# spielfeld_anzeige.net
KiCad netlist of a schematic drawn in EAGLE
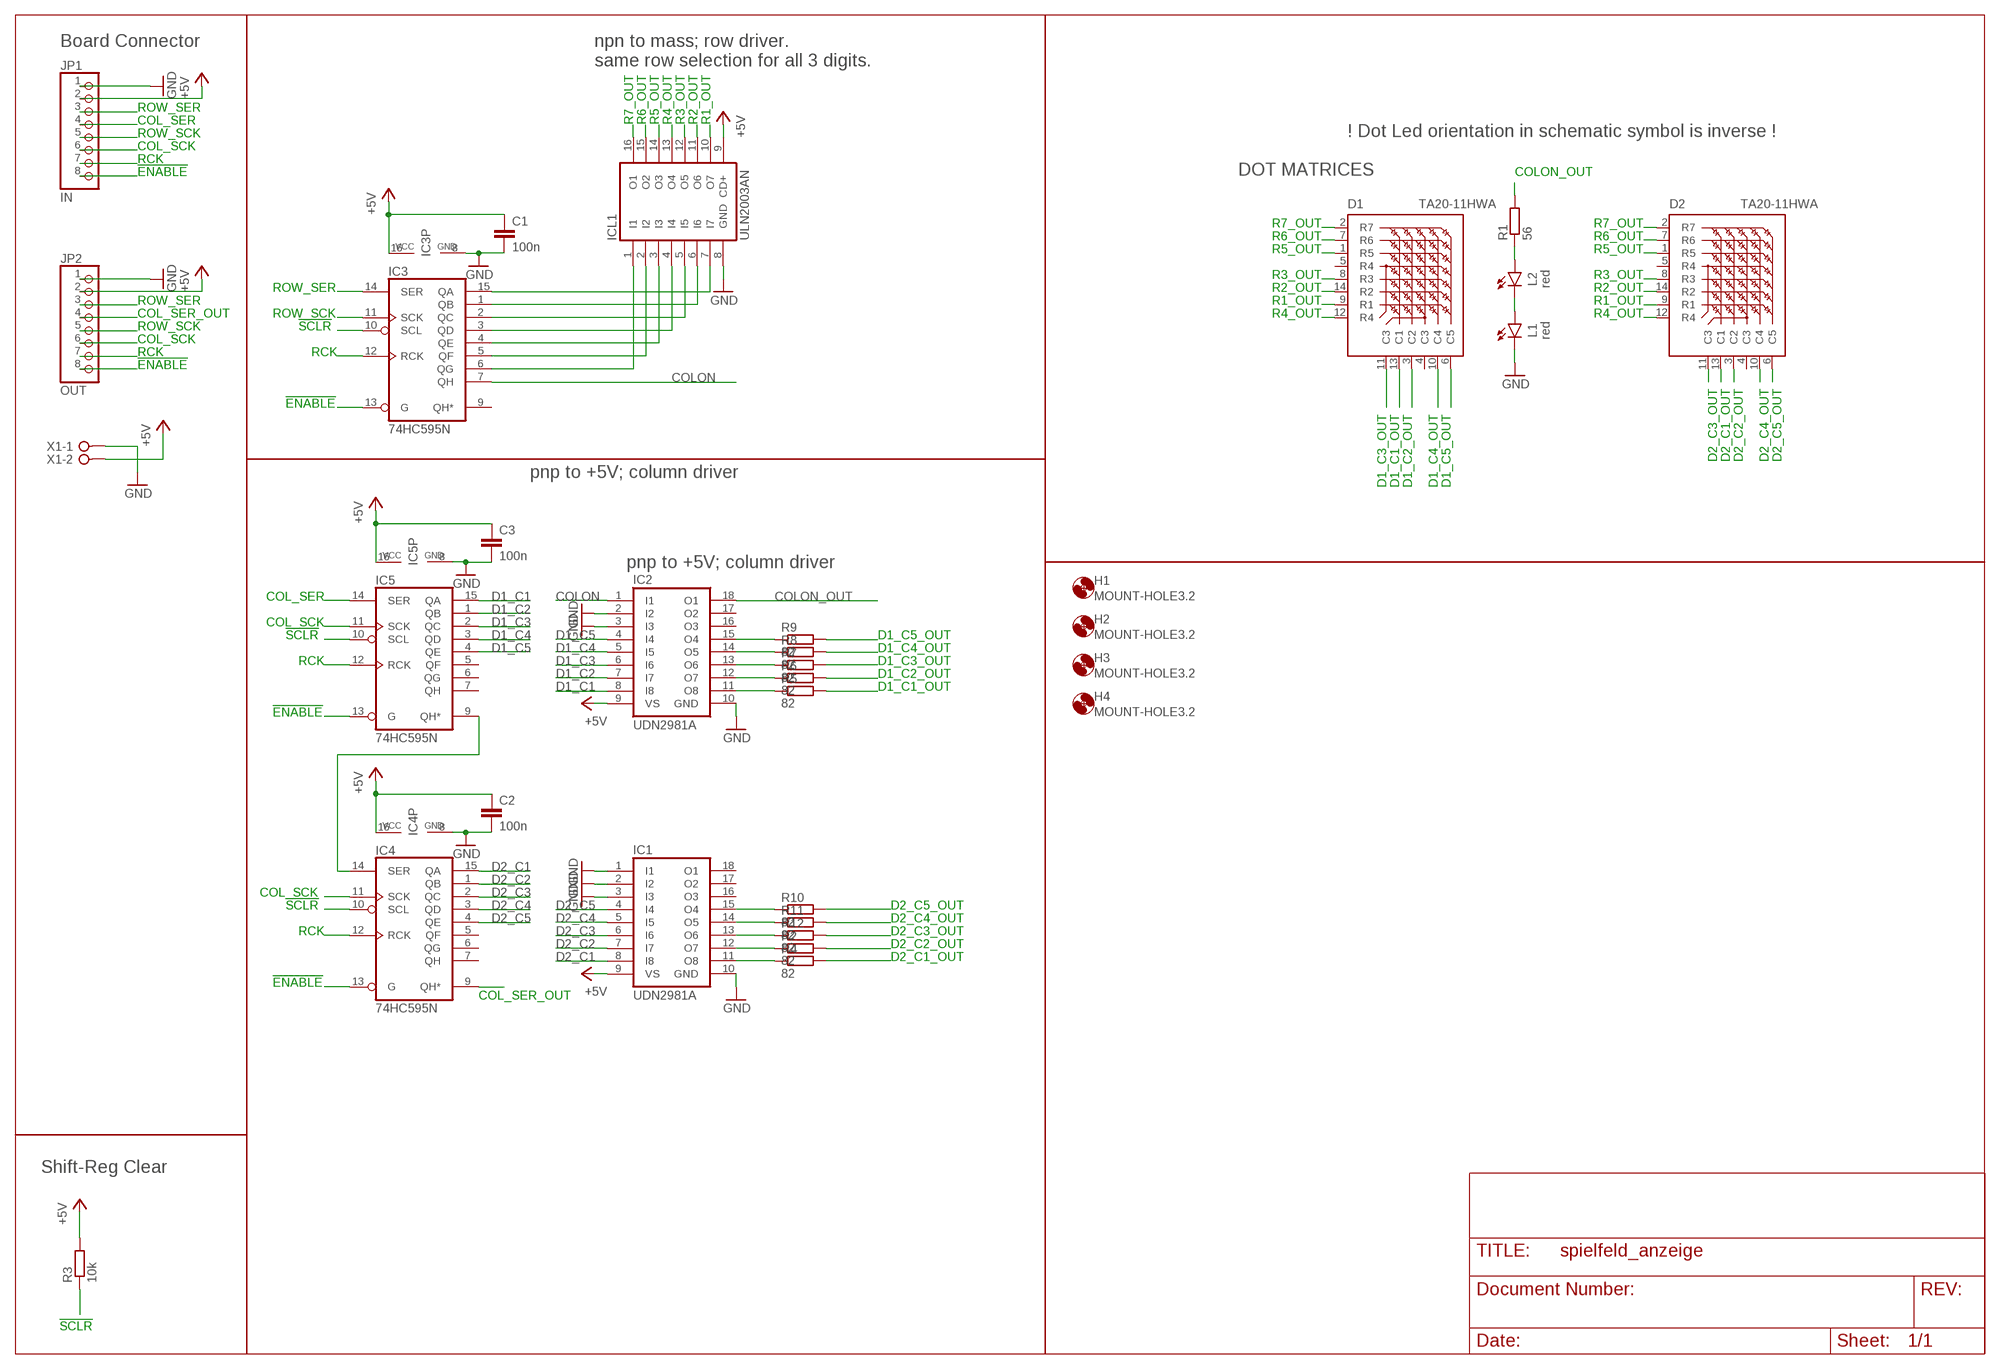
[diagram p0: schematic, sheet 1]

(export (version "E")
  (design (tool "Eeschema 10.0.6"))
  (components
    (comp (ref "C1")
      (value "100n")
      (footprint "eagle-import:C0805")
      (libsource (lib "eagle-import") (part "C-EUC0805"))
    )
    (comp (ref "C2")
      (value "100n")
      (footprint "eagle-import:C0805")
      (libsource (lib "eagle-import") (part "C-EUC0805"))
    )
    (comp (ref "C3")
      (value "100n")
      (footprint "eagle-import:C0805")
      (libsource (lib "eagle-import") (part "C-EUC0805"))
    )
    (comp (ref "D1")
      (value "TA20-11HWA")
      (footprint "eagle-import:TA20-11HWA")
      (libsource (lib "eagle-import") (part "TA20-11HWA"))
    )
    (comp (ref "D2")
      (value "TA20-11HWA")
      (footprint "eagle-import:TA20-11HWA")
      (libsource (lib "eagle-import") (part "TA20-11HWA"))
    )
    (comp (ref "H1")
      (value "MOUNT-HOLE3.2")
      (footprint "eagle-import:3,2")
      (libsource (lib "eagle-import") (part "MOUNT-HOLE3.2"))
    )
    (comp (ref "H2")
      (value "MOUNT-HOLE3.2")
      (footprint "eagle-import:3,2")
      (libsource (lib "eagle-import") (part "MOUNT-HOLE3.2"))
    )
    (comp (ref "H3")
      (value "MOUNT-HOLE3.2")
      (footprint "eagle-import:3,2")
      (libsource (lib "eagle-import") (part "MOUNT-HOLE3.2"))
    )
    (comp (ref "H4")
      (value "MOUNT-HOLE3.2")
      (footprint "eagle-import:3,2")
      (libsource (lib "eagle-import") (part "MOUNT-HOLE3.2"))
    )
    (comp (ref "IC1")
      (value "UDN2981A")
      (footprint "eagle-import:DIL18")
      (libsource (lib "eagle-import") (part "UDN298A1"))
    )
    (comp (ref "IC2")
      (value "UDN2981A")
      (footprint "eagle-import:DIL18")
      (libsource (lib "eagle-import") (part "UDN298A1"))
    )
    (comp (ref "IC3")
      (value "74HC595N")
      (footprint "eagle-import:DIL16")
      (libsource (lib "eagle-import") (part "74595NHC"))
    )
    (comp (ref "IC4")
      (value "74HC595N")
      (footprint "eagle-import:DIL16")
      (libsource (lib "eagle-import") (part "74595NHC"))
    )
    (comp (ref "IC5")
      (value "74HC595N")
      (footprint "eagle-import:DIL16")
      (libsource (lib "eagle-import") (part "74595NHC"))
    )
    (comp (ref "ICL1")
      (value "ULN2003AN")
      (footprint "eagle-import:DIL16")
      (libsource (lib "eagle-import") (part "ULN2003AN"))
    )
    (comp (ref "JP1")
      (value "IN")
      (footprint "eagle-import:1X08")
      (libsource (lib "eagle-import") (part "PINHD-1X8"))
    )
    (comp (ref "JP2")
      (value "OUT")
      (footprint "eagle-import:1X08")
      (libsource (lib "eagle-import") (part "PINHD-1X8"))
    )
    (comp (ref "L1")
      (value "red")
      (footprint "eagle-import:LED_5MM")
      (libsource (lib "eagle-import") (part "LED-5MM"))
    )
    (comp (ref "L2")
      (value "red")
      (footprint "eagle-import:LED_5MM")
      (libsource (lib "eagle-import") (part "LED-5MM"))
    )
    (comp (ref "R1")
      (value "56")
      (footprint "eagle-import:R3216")
      (libsource (lib "eagle-import") (part "R-EU_R3216"))
    )
    (comp (ref "R2")
      (value "82")
      (footprint "eagle-import:R0805")
      (libsource (lib "eagle-import") (part "R-EU_R0805"))
    )
    (comp (ref "R3")
      (value "10k")
      (footprint "eagle-import:M3216")
      (libsource (lib "eagle-import") (part "resistor_R-EU_M3216"))
    )
    (comp (ref "R4")
      (value "82")
      (footprint "eagle-import:R0805")
      (libsource (lib "eagle-import") (part "R-EU_R0805"))
    )
    (comp (ref "R5")
      (value "82")
      (footprint "eagle-import:R0805")
      (libsource (lib "eagle-import") (part "R-EU_R0805"))
    )
    (comp (ref "R6")
      (value "82")
      (footprint "eagle-import:R0805")
      (libsource (lib "eagle-import") (part "R-EU_R0805"))
    )
    (comp (ref "R7")
      (value "82")
      (footprint "eagle-import:R0805")
      (libsource (lib "eagle-import") (part "R-EU_R0805"))
    )
    (comp (ref "R8")
      (value "82")
      (footprint "eagle-import:R0805")
      (libsource (lib "eagle-import") (part "R-EU_R0805"))
    )
    (comp (ref "R9")
      (value "82")
      (footprint "eagle-import:R0805")
      (libsource (lib "eagle-import") (part "R-EU_R0805"))
    )
    (comp (ref "R10")
      (value "82")
      (footprint "eagle-import:R0805")
      (libsource (lib "eagle-import") (part "R-EU_R0805"))
    )
    (comp (ref "R11")
      (value "82")
      (footprint "eagle-import:R0805")
      (libsource (lib "eagle-import") (part "R-EU_R0805"))
    )
    (comp (ref "R12")
      (value "82")
      (footprint "eagle-import:R0805")
      (libsource (lib "eagle-import") (part "R-EU_R0805"))
    )
    (comp (ref "X1")
      (value "W237-02P")
      (footprint "eagle-import:W237-132")
      (libsource (lib "eagle-import") (part "W237-02P"))
    )
  )
  (nets
    (net (code "1") (name "+5V") (class "Default")
      (node (ref "C1") (pin "1") (pinfunction "1_1") (pintype "passive"))
      (node (ref "C2") (pin "1") (pinfunction "1_1") (pintype "passive"))
      (node (ref "C3") (pin "1") (pinfunction "1_1") (pintype "passive"))
      (node (ref "IC1") (pin "9") (pinfunction "VS_9") (pintype "passive"))
      (node (ref "IC2") (pin "9") (pinfunction "VS_9") (pintype "passive"))
      (node (ref "IC3") (pin "16") (pinfunction "VCC_16") (pintype "power_in"))
      (node (ref "IC4") (pin "16") (pinfunction "VCC_16") (pintype "power_in"))
      (node (ref "IC5") (pin "16") (pinfunction "VCC_16") (pintype "power_in"))
      (node (ref "ICL1") (pin "9") (pinfunction "CD+_9") (pintype "passive"))
      (node (ref "JP1") (pin "2") (pinfunction "2_2") (pintype "passive"))
      (node (ref "JP2") (pin "2") (pinfunction "2_2") (pintype "passive"))
      (node (ref "R3") (pin "2") (pinfunction "2_2") (pintype "passive"))
      (node (ref "X1") (pin "2") (pinfunction "KL_2") (pintype "passive"))
    )
    (net (code "2") (name "/COLON") (class "Default")
      (node (ref "IC2") (pin "1") (pinfunction "I1_1") (pintype "input"))
      (node (ref "IC3") (pin "7") (pinfunction "QH_7") (pintype "tri_state"))
    )
    (net (code "3") (name "/COLON_OUT") (class "Default")
      (node (ref "IC2") (pin "18") (pinfunction "O1_18") (pintype "open_collector"))
      (node (ref "R1") (pin "2") (pinfunction "2_2") (pintype "passive"))
    )
    (net (code "4") (name "/COL_SCK") (class "Default")
      (node (ref "IC4") (pin "11") (pinfunction "SCK_11") (pintype "input"))
      (node (ref "IC5") (pin "11") (pinfunction "SCK_11") (pintype "input"))
      (node (ref "JP1") (pin "6") (pinfunction "6_6") (pintype "passive"))
      (node (ref "JP2") (pin "6") (pinfunction "6_6") (pintype "passive"))
    )
    (net (code "5") (name "/COL_SER") (class "Default")
      (node (ref "IC5") (pin "14") (pinfunction "SER_14") (pintype "input"))
      (node (ref "JP1") (pin "4") (pinfunction "4_4") (pintype "passive"))
    )
    (net (code "6") (name "/COL_SER_OUT") (class "Default")
      (node (ref "IC4") (pin "9") (pinfunction "QH*_9") (pintype "tri_state"))
      (node (ref "JP2") (pin "4") (pinfunction "4_4") (pintype "passive"))
    )
    (net (code "7") (name "/D1_C1") (class "Default")
      (node (ref "IC2") (pin "8") (pinfunction "I8_8") (pintype "input"))
      (node (ref "IC5") (pin "15") (pinfunction "QA_15") (pintype "tri_state"))
    )
    (net (code "8") (name "/D1_C1_OUT") (class "Default")
      (node (ref "D1") (pin "13") (pinfunction "C1_13") (pintype "passive"))
      (node (ref "R5") (pin "2") (pinfunction "2_2") (pintype "passive"))
    )
    (net (code "9") (name "/D1_C2") (class "Default")
      (node (ref "IC2") (pin "7") (pinfunction "I7_7") (pintype "input"))
      (node (ref "IC5") (pin "1") (pinfunction "QB_1") (pintype "tri_state"))
    )
    (net (code "10") (name "/D1_C2_OUT") (class "Default")
      (node (ref "D1") (pin "3") (pinfunction "C2_3") (pintype "passive"))
      (node (ref "R6") (pin "2") (pinfunction "2_2") (pintype "passive"))
    )
    (net (code "11") (name "/D1_C3") (class "Default")
      (node (ref "IC2") (pin "6") (pinfunction "I6_6") (pintype "input"))
      (node (ref "IC5") (pin "2") (pinfunction "QC_2") (pintype "tri_state"))
    )
    (net (code "12") (name "/D1_C3_OUT") (class "Default")
      (node (ref "D1") (pin "11") (pinfunction "C3_11") (pintype "passive"))
      (node (ref "R7") (pin "2") (pinfunction "2_2") (pintype "passive"))
    )
    (net (code "13") (name "/D1_C4") (class "Default")
      (node (ref "IC2") (pin "5") (pinfunction "I5_5") (pintype "input"))
      (node (ref "IC5") (pin "3") (pinfunction "QD_3") (pintype "tri_state"))
    )
    (net (code "14") (name "/D1_C4_OUT") (class "Default")
      (node (ref "D1") (pin "10") (pinfunction "C4_10") (pintype "passive"))
      (node (ref "R8") (pin "2") (pinfunction "2_2") (pintype "passive"))
    )
    (net (code "15") (name "/D1_C5") (class "Default")
      (node (ref "IC2") (pin "4") (pinfunction "I4_4") (pintype "input"))
      (node (ref "IC5") (pin "4") (pinfunction "QE_4") (pintype "tri_state"))
    )
    (net (code "16") (name "/D1_C5_OUT") (class "Default")
      (node (ref "D1") (pin "6") (pinfunction "C5_6") (pintype "passive"))
      (node (ref "R9") (pin "2") (pinfunction "2_2") (pintype "passive"))
    )
    (net (code "17") (name "/D2_C1") (class "Default")
      (node (ref "IC1") (pin "8") (pinfunction "I8_8") (pintype "input"))
      (node (ref "IC4") (pin "15") (pinfunction "QA_15") (pintype "tri_state"))
    )
    (net (code "18") (name "/D2_C1_OUT") (class "Default")
      (node (ref "D2") (pin "13") (pinfunction "C1_13") (pintype "passive"))
      (node (ref "R4") (pin "2") (pinfunction "2_2") (pintype "passive"))
    )
    (net (code "19") (name "/D2_C2") (class "Default")
      (node (ref "IC1") (pin "7") (pinfunction "I7_7") (pintype "input"))
      (node (ref "IC4") (pin "1") (pinfunction "QB_1") (pintype "tri_state"))
    )
    (net (code "20") (name "/D2_C2_OUT") (class "Default")
      (node (ref "D2") (pin "3") (pinfunction "C2_3") (pintype "passive"))
      (node (ref "R2") (pin "2") (pinfunction "2_2") (pintype "passive"))
    )
    (net (code "21") (name "/D2_C3") (class "Default")
      (node (ref "IC1") (pin "6") (pinfunction "I6_6") (pintype "input"))
      (node (ref "IC4") (pin "2") (pinfunction "QC_2") (pintype "tri_state"))
    )
    (net (code "22") (name "/D2_C3_OUT") (class "Default")
      (node (ref "D2") (pin "11") (pinfunction "C3_11") (pintype "passive"))
      (node (ref "R12") (pin "2") (pinfunction "2_2") (pintype "passive"))
    )
    (net (code "23") (name "/D2_C4") (class "Default")
      (node (ref "IC1") (pin "5") (pinfunction "I5_5") (pintype "input"))
      (node (ref "IC4") (pin "3") (pinfunction "QD_3") (pintype "tri_state"))
    )
    (net (code "24") (name "/D2_C4_OUT") (class "Default")
      (node (ref "D2") (pin "10") (pinfunction "C4_10") (pintype "passive"))
      (node (ref "R11") (pin "2") (pinfunction "2_2") (pintype "passive"))
    )
    (net (code "25") (name "/D2_C5") (class "Default")
      (node (ref "IC1") (pin "4") (pinfunction "I4_4") (pintype "input"))
      (node (ref "IC4") (pin "4") (pinfunction "QE_4") (pintype "tri_state"))
    )
    (net (code "26") (name "/D2_C5_OUT") (class "Default")
      (node (ref "D2") (pin "6") (pinfunction "C5_6") (pintype "passive"))
      (node (ref "R10") (pin "2") (pinfunction "2_2") (pintype "passive"))
    )
    (net (code "27") (name "/R1_OUT") (class "Default")
      (node (ref "D1") (pin "9") (pinfunction "R1_9") (pintype "passive"))
      (node (ref "D2") (pin "9") (pinfunction "R1_9") (pintype "passive"))
      (node (ref "ICL1") (pin "10") (pinfunction "O7_10") (pintype "open_collector"))
    )
    (net (code "28") (name "/R2_OUT") (class "Default")
      (node (ref "D1") (pin "14") (pinfunction "R2_14") (pintype "passive"))
      (node (ref "D2") (pin "14") (pinfunction "R2_14") (pintype "passive"))
      (node (ref "ICL1") (pin "11") (pinfunction "O6_11") (pintype "open_collector"))
    )
    (net (code "29") (name "/R3_OUT") (class "Default")
      (node (ref "D1") (pin "8") (pinfunction "R3_8") (pintype "passive"))
      (node (ref "D2") (pin "8") (pinfunction "R3_8") (pintype "passive"))
      (node (ref "ICL1") (pin "12") (pinfunction "O5_12") (pintype "open_collector"))
    )
    (net (code "30") (name "/R4_OUT") (class "Default")
      (node (ref "D1") (pin "12") (pinfunction "R4_12") (pintype "passive"))
      (node (ref "D2") (pin "12") (pinfunction "R4_12") (pintype "passive"))
      (node (ref "ICL1") (pin "13") (pinfunction "O4_13") (pintype "open_collector"))
    )
    (net (code "31") (name "/R5_OUT") (class "Default")
      (node (ref "D1") (pin "1") (pinfunction "R5_1") (pintype "passive"))
      (node (ref "D2") (pin "1") (pinfunction "R5_1") (pintype "passive"))
      (node (ref "ICL1") (pin "14") (pinfunction "O3_14") (pintype "open_collector"))
    )
    (net (code "32") (name "/R6_OUT") (class "Default")
      (node (ref "D1") (pin "7") (pinfunction "R6_7") (pintype "passive"))
      (node (ref "D2") (pin "7") (pinfunction "R6_7") (pintype "passive"))
      (node (ref "ICL1") (pin "15") (pinfunction "O2_15") (pintype "open_collector"))
    )
    (net (code "33") (name "/R7_OUT") (class "Default")
      (node (ref "D1") (pin "2") (pinfunction "R7_2") (pintype "passive"))
      (node (ref "D2") (pin "2") (pinfunction "R7_2") (pintype "passive"))
      (node (ref "ICL1") (pin "16") (pinfunction "O1_16") (pintype "open_collector"))
    )
    (net (code "34") (name "/RCK") (class "Default")
      (node (ref "IC3") (pin "12") (pinfunction "RCK_12") (pintype "input"))
      (node (ref "IC4") (pin "12") (pinfunction "RCK_12") (pintype "input"))
      (node (ref "IC5") (pin "12") (pinfunction "RCK_12") (pintype "input"))
      (node (ref "JP1") (pin "7") (pinfunction "7_7") (pintype "passive"))
      (node (ref "JP2") (pin "7") (pinfunction "7_7") (pintype "passive"))
    )
    (net (code "35") (name "/ROW_SCK") (class "Default")
      (node (ref "IC3") (pin "11") (pinfunction "SCK_11") (pintype "input"))
      (node (ref "JP1") (pin "5") (pinfunction "5_5") (pintype "passive"))
      (node (ref "JP2") (pin "5") (pinfunction "5_5") (pintype "passive"))
    )
    (net (code "36") (name "/ROW_SER") (class "Default")
      (node (ref "IC3") (pin "14") (pinfunction "SER_14") (pintype "input"))
      (node (ref "JP1") (pin "3") (pinfunction "3_3") (pintype "passive"))
      (node (ref "JP2") (pin "3") (pinfunction "3_3") (pintype "passive"))
    )
    (net (code "37") (name "/~{ENABLE}") (class "Default")
      (node (ref "IC3") (pin "13") (pinfunction "G_13") (pintype "input"))
      (node (ref "IC4") (pin "13") (pinfunction "G_13") (pintype "input"))
      (node (ref "IC5") (pin "13") (pinfunction "G_13") (pintype "input"))
      (node (ref "JP1") (pin "8") (pinfunction "8_8") (pintype "passive"))
      (node (ref "JP2") (pin "8") (pinfunction "8_8") (pintype "passive"))
    )
    (net (code "38") (name "/~{SCLR}") (class "Default")
      (node (ref "IC3") (pin "10") (pinfunction "SCL_10") (pintype "input"))
      (node (ref "IC4") (pin "10") (pinfunction "SCL_10") (pintype "input"))
      (node (ref "IC5") (pin "10") (pinfunction "SCL_10") (pintype "input"))
      (node (ref "R3") (pin "1") (pinfunction "1_1") (pintype "passive"))
    )
    (net (code "39") (name "GND") (class "Default")
      (node (ref "C1") (pin "2") (pinfunction "2_2") (pintype "passive"))
      (node (ref "C2") (pin "2") (pinfunction "2_2") (pintype "passive"))
      (node (ref "C3") (pin "2") (pinfunction "2_2") (pintype "passive"))
      (node (ref "IC1") (pin "1") (pinfunction "I1_1") (pintype "input"))
      (node (ref "IC1") (pin "10") (pinfunction "GND_10") (pintype "power_in"))
      (node (ref "IC1") (pin "2") (pinfunction "I2_2") (pintype "input"))
      (node (ref "IC1") (pin "3") (pinfunction "I3_3") (pintype "input"))
      (node (ref "IC2") (pin "10") (pinfunction "GND_10") (pintype "power_in"))
      (node (ref "IC2") (pin "2") (pinfunction "I2_2") (pintype "input"))
      (node (ref "IC2") (pin "3") (pinfunction "I3_3") (pintype "input"))
      (node (ref "IC3") (pin "8") (pinfunction "GND_8") (pintype "power_in"))
      (node (ref "IC4") (pin "8") (pinfunction "GND_8") (pintype "power_in"))
      (node (ref "IC5") (pin "8") (pinfunction "GND_8") (pintype "power_in"))
      (node (ref "ICL1") (pin "8") (pinfunction "GND_8") (pintype "power_in"))
      (node (ref "JP1") (pin "1") (pinfunction "1_1") (pintype "passive"))
      (node (ref "JP2") (pin "1") (pinfunction "1_1") (pintype "passive"))
      (node (ref "L1") (pin "K") (pinfunction "C_K") (pintype "passive"))
      (node (ref "X1") (pin "1") (pinfunction "KL_1") (pintype "passive"))
    )
    (net (code "40") (name "Net-(IC1-O4)") (class "Default")
      (node (ref "IC1") (pin "15") (pinfunction "O4_15") (pintype "open_collector"))
      (node (ref "R10") (pin "1") (pinfunction "1_1") (pintype "passive"))
    )
    (net (code "41") (name "Net-(IC1-O5)") (class "Default")
      (node (ref "IC1") (pin "14") (pinfunction "O5_14") (pintype "open_collector"))
      (node (ref "R11") (pin "1") (pinfunction "1_1") (pintype "passive"))
    )
    (net (code "42") (name "Net-(IC1-O6)") (class "Default")
      (node (ref "IC1") (pin "13") (pinfunction "O6_13") (pintype "open_collector"))
      (node (ref "R12") (pin "1") (pinfunction "1_1") (pintype "passive"))
    )
    (net (code "43") (name "Net-(IC1-O7)") (class "Default")
      (node (ref "IC1") (pin "12") (pinfunction "O7_12") (pintype "open_collector"))
      (node (ref "R2") (pin "1") (pinfunction "1_1") (pintype "passive"))
    )
    (net (code "44") (name "Net-(IC1-O8)") (class "Default")
      (node (ref "IC1") (pin "11") (pinfunction "O8_11") (pintype "open_collector"))
      (node (ref "R4") (pin "1") (pinfunction "1_1") (pintype "passive"))
    )
    (net (code "45") (name "Net-(IC2-O4)") (class "Default")
      (node (ref "IC2") (pin "15") (pinfunction "O4_15") (pintype "open_collector"))
      (node (ref "R9") (pin "1") (pinfunction "1_1") (pintype "passive"))
    )
    (net (code "46") (name "Net-(IC2-O5)") (class "Default")
      (node (ref "IC2") (pin "14") (pinfunction "O5_14") (pintype "open_collector"))
      (node (ref "R8") (pin "1") (pinfunction "1_1") (pintype "passive"))
    )
    (net (code "47") (name "Net-(IC2-O6)") (class "Default")
      (node (ref "IC2") (pin "13") (pinfunction "O6_13") (pintype "open_collector"))
      (node (ref "R7") (pin "1") (pinfunction "1_1") (pintype "passive"))
    )
    (net (code "48") (name "Net-(IC2-O7)") (class "Default")
      (node (ref "IC2") (pin "12") (pinfunction "O7_12") (pintype "open_collector"))
      (node (ref "R6") (pin "1") (pinfunction "1_1") (pintype "passive"))
    )
    (net (code "49") (name "Net-(IC2-O8)") (class "Default")
      (node (ref "IC2") (pin "11") (pinfunction "O8_11") (pintype "open_collector"))
      (node (ref "R5") (pin "1") (pinfunction "1_1") (pintype "passive"))
    )
    (net (code "50") (name "Net-(IC3A-QA)") (class "Default")
      (node (ref "IC3") (pin "15") (pinfunction "QA_15") (pintype "tri_state"))
      (node (ref "ICL1") (pin "7") (pinfunction "I7_7") (pintype "input"))
    )
    (net (code "51") (name "Net-(IC3A-QB)") (class "Default")
      (node (ref "IC3") (pin "1") (pinfunction "QB_1") (pintype "tri_state"))
      (node (ref "ICL1") (pin "6") (pinfunction "I6_6") (pintype "input"))
    )
    (net (code "52") (name "Net-(IC3A-QC)") (class "Default")
      (node (ref "IC3") (pin "2") (pinfunction "QC_2") (pintype "tri_state"))
      (node (ref "ICL1") (pin "5") (pinfunction "I5_5") (pintype "input"))
    )
    (net (code "53") (name "Net-(IC3A-QD)") (class "Default")
      (node (ref "IC3") (pin "3") (pinfunction "QD_3") (pintype "tri_state"))
      (node (ref "ICL1") (pin "4") (pinfunction "I4_4") (pintype "input"))
    )
    (net (code "54") (name "Net-(IC3A-QE)") (class "Default")
      (node (ref "IC3") (pin "4") (pinfunction "QE_4") (pintype "tri_state"))
      (node (ref "ICL1") (pin "3") (pinfunction "I3_3") (pintype "input"))
    )
    (net (code "55") (name "Net-(IC3A-QF)") (class "Default")
      (node (ref "IC3") (pin "5") (pinfunction "QF_5") (pintype "tri_state"))
      (node (ref "ICL1") (pin "2") (pinfunction "I2_2") (pintype "input"))
    )
    (net (code "56") (name "Net-(IC3A-QG)") (class "Default")
      (node (ref "IC3") (pin "6") (pinfunction "QG_6") (pintype "tri_state"))
      (node (ref "ICL1") (pin "1") (pinfunction "I1_1") (pintype "input"))
    )
    (net (code "57") (name "Net-(IC4A-SER)") (class "Default")
      (node (ref "IC4") (pin "14") (pinfunction "SER_14") (pintype "input"))
      (node (ref "IC5") (pin "9") (pinfunction "QH*_9") (pintype "tri_state"))
    )
    (net (code "58") (name "Net-(L2-C)") (class "Default")
      (node (ref "L1") (pin "A") (pinfunction "A_A") (pintype "passive"))
      (node (ref "L2") (pin "K") (pinfunction "C_K") (pintype "passive"))
    )
    (net (code "59") (name "Net-(L2-PadA)") (class "Default")
      (node (ref "L2") (pin "A") (pinfunction "A_A") (pintype "passive"))
      (node (ref "R1") (pin "1") (pinfunction "1_1") (pintype "passive"))
    )
    (net (code "60") (name "unconnected-(D1-C3-Pad4)") (class "Default")
      (node (ref "D1") (pin "4") (pinfunction "C3_4") (pintype "passive"))
    )
    (net (code "61") (name "unconnected-(D1-R4-Pad5)") (class "Default")
      (node (ref "D1") (pin "5") (pinfunction "R4_5") (pintype "passive"))
    )
    (net (code "62") (name "unconnected-(D2-C3-Pad4)") (class "Default")
      (node (ref "D2") (pin "4") (pinfunction "C3_4") (pintype "passive"))
    )
    (net (code "63") (name "unconnected-(D2-R4-Pad5)") (class "Default")
      (node (ref "D2") (pin "5") (pinfunction "R4_5") (pintype "passive"))
    )
    (net (code "64") (name "unconnected-(IC1-O1-Pad18)") (class "Default")
      (node (ref "IC1") (pin "18") (pinfunction "O1_18") (pintype "open_collector"))
    )
    (net (code "65") (name "unconnected-(IC1-O2-Pad17)") (class "Default")
      (node (ref "IC1") (pin "17") (pinfunction "O2_17") (pintype "open_collector"))
    )
    (net (code "66") (name "unconnected-(IC1-O3-Pad16)") (class "Default")
      (node (ref "IC1") (pin "16") (pinfunction "O3_16") (pintype "open_collector"))
    )
    (net (code "67") (name "unconnected-(IC2-O2-Pad17)") (class "Default")
      (node (ref "IC2") (pin "17") (pinfunction "O2_17") (pintype "open_collector"))
    )
    (net (code "68") (name "unconnected-(IC2-O3-Pad16)") (class "Default")
      (node (ref "IC2") (pin "16") (pinfunction "O3_16") (pintype "open_collector"))
    )
    (net (code "69") (name "unconnected-(IC3A-QH*-Pad9)") (class "Default")
      (node (ref "IC3") (pin "9") (pinfunction "QH*_9") (pintype "tri_state"))
    )
    (net (code "70") (name "unconnected-(IC4A-QF-Pad5)") (class "Default")
      (node (ref "IC4") (pin "5") (pinfunction "QF_5") (pintype "tri_state"))
    )
    (net (code "71") (name "unconnected-(IC4A-QG-Pad6)") (class "Default")
      (node (ref "IC4") (pin "6") (pinfunction "QG_6") (pintype "tri_state"))
    )
    (net (code "72") (name "unconnected-(IC4A-QH-Pad7)") (class "Default")
      (node (ref "IC4") (pin "7") (pinfunction "QH_7") (pintype "tri_state"))
    )
    (net (code "73") (name "unconnected-(IC5A-QF-Pad5)") (class "Default")
      (node (ref "IC5") (pin "5") (pinfunction "QF_5") (pintype "tri_state"))
    )
    (net (code "74") (name "unconnected-(IC5A-QG-Pad6)") (class "Default")
      (node (ref "IC5") (pin "6") (pinfunction "QG_6") (pintype "tri_state"))
    )
    (net (code "75") (name "unconnected-(IC5A-QH-Pad7)") (class "Default")
      (node (ref "IC5") (pin "7") (pinfunction "QH_7") (pintype "tri_state"))
    )
  )
)
